# Radii.net
KiCad netlist of a schematic drawn in EAGLE
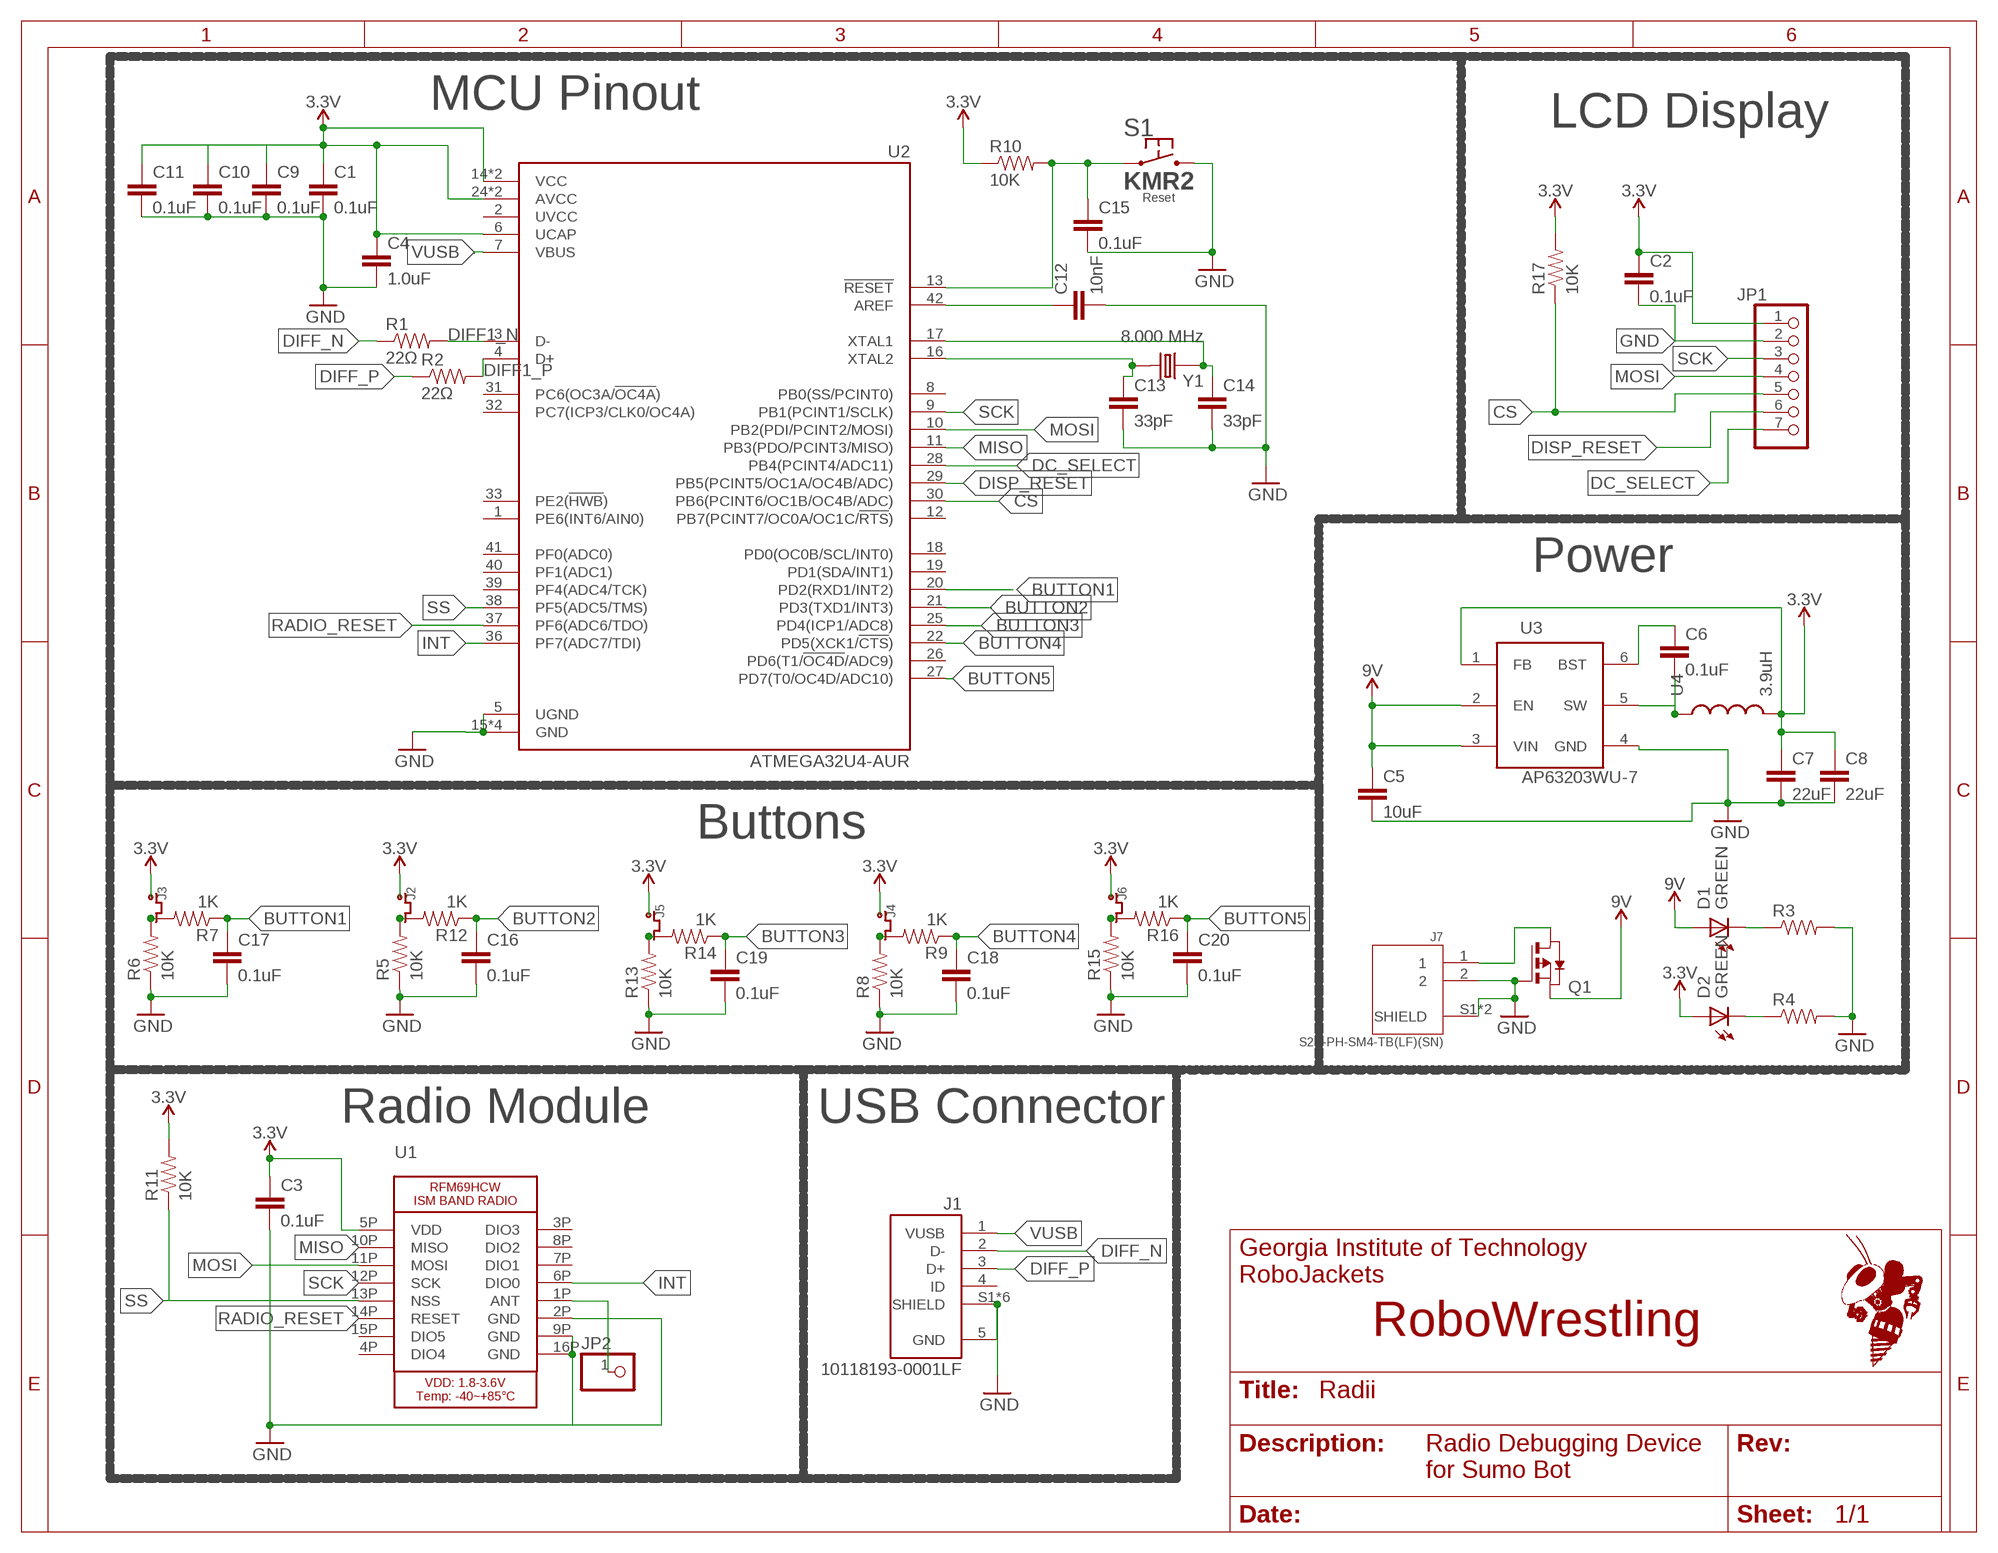
[diagram p0: schematic, sheet 1]

(export (version "E")
  (design (tool "Eeschema 10.0.6"))
  (components
    (comp (ref "C1")
      (value "0.1uF")
      (footprint "eagle-import:0603")
      (libsource (lib "eagle-import") (part "0.1UF-0603-25V-(+80/-20%)"))
    )
    (comp (ref "C2")
      (value "0.1uF")
      (footprint "eagle-import:0603")
      (libsource (lib "eagle-import") (part "0.1UF-0603-25V-(+80/-20%)"))
    )
    (comp (ref "C3")
      (value "0.1uF")
      (footprint "eagle-import:0603")
      (libsource (lib "eagle-import") (part "0.1UF-0603-25V-(+80/-20%)"))
    )
    (comp (ref "C4")
      (value "1.0uF")
      (footprint "eagle-import:0603")
      (libsource (lib "eagle-import") (part "1.0UF-0603-16V-10%"))
    )
    (comp (ref "C5")
      (value "10uF")
      (footprint "eagle-import:0603")
      (libsource (lib "eagle-import") (part "10UF-0603-6.3V-20%"))
    )
    (comp (ref "C6")
      (value "0.1uF")
      (footprint "eagle-import:0603")
      (libsource (lib "eagle-import") (part "0.1UF-0603-25V-(+80/-20%)"))
    )
    (comp (ref "C7")
      (value "22uF")
      (footprint "eagle-import:1210")
      (libsource (lib "eagle-import") (part "22UF-1210-16V-20%"))
    )
    (comp (ref "C8")
      (value "22uF")
      (footprint "eagle-import:1210")
      (libsource (lib "eagle-import") (part "22UF-1210-16V-20%"))
    )
    (comp (ref "C9")
      (value "0.1uF")
      (footprint "eagle-import:0603")
      (libsource (lib "eagle-import") (part "0.1UF-0603-25V-(+80/-20%)"))
    )
    (comp (ref "C10")
      (value "0.1uF")
      (footprint "eagle-import:0603")
      (libsource (lib "eagle-import") (part "0.1UF-0603-25V-(+80/-20%)"))
    )
    (comp (ref "C11")
      (value "0.1uF")
      (footprint "eagle-import:0603")
      (libsource (lib "eagle-import") (part "0.1UF-0603-25V-(+80/-20%)"))
    )
    (comp (ref "C12")
      (value "10nF")
      (footprint "eagle-import:0603")
      (libsource (lib "eagle-import") (part "10NF-0603-50V-10%"))
    )
    (comp (ref "C13")
      (value "33pF")
      (footprint "eagle-import:0603")
      (libsource (lib "eagle-import") (part "33PF-0603-50V-5%"))
    )
    (comp (ref "C14")
      (value "33pF")
      (footprint "eagle-import:0603")
      (libsource (lib "eagle-import") (part "33PF-0603-50V-5%"))
    )
    (comp (ref "C15")
      (value "0.1uF")
      (footprint "eagle-import:0603")
      (libsource (lib "eagle-import") (part "0.1UF-0603-25V-(+80/-20%)"))
    )
    (comp (ref "C16")
      (value "0.1uF")
      (footprint "eagle-import:0603")
      (libsource (lib "eagle-import") (part "0.1UF-0603-25V-(+80/-20%)"))
    )
    (comp (ref "C17")
      (value "0.1uF")
      (footprint "eagle-import:0603")
      (libsource (lib "eagle-import") (part "0.1UF-0603-25V-(+80/-20%)"))
    )
    (comp (ref "C18")
      (value "0.1uF")
      (footprint "eagle-import:0603")
      (libsource (lib "eagle-import") (part "0.1UF-0603-25V-(+80/-20%)"))
    )
    (comp (ref "C19")
      (value "0.1uF")
      (footprint "eagle-import:0603")
      (libsource (lib "eagle-import") (part "0.1UF-0603-25V-(+80/-20%)"))
    )
    (comp (ref "C20")
      (value "0.1uF")
      (footprint "eagle-import:0603")
      (libsource (lib "eagle-import") (part "0.1UF-0603-25V-(+80/-20%)"))
    )
    (comp (ref "D1")
      (value "GREEN")
      (footprint "eagle-import:CHIP-LED0603")
      (libsource (lib "eagle-import") (part "LED-SMD"))
    )
    (comp (ref "D2")
      (value "GREEN")
      (footprint "eagle-import:CHIP-LED0603")
      (libsource (lib "eagle-import") (part "LED-SMD"))
    )
    (comp (ref "J1")
      (value "10118193-0001LF")
      (footprint "eagle-import:FCI_10118193-0001LF")
      (libsource (lib "eagle-import") (part "10118193-0001LF"))
    )
    (comp (ref "J2")
      (value "BUTTON")
      (footprint "eagle-import:1X02")
      (libsource (lib "eagle-import") (part "BUTTON"))
    )
    (comp (ref "J3")
      (value "BUTTON")
      (footprint "eagle-import:1X02")
      (libsource (lib "eagle-import") (part "BUTTON"))
    )
    (comp (ref "J4")
      (value "BUTTON")
      (footprint "eagle-import:1X02")
      (libsource (lib "eagle-import") (part "BUTTON"))
    )
    (comp (ref "J5")
      (value "BUTTON")
      (footprint "eagle-import:1X02")
      (libsource (lib "eagle-import") (part "BUTTON"))
    )
    (comp (ref "J6")
      (value "BUTTON")
      (footprint "eagle-import:1X02")
      (libsource (lib "eagle-import") (part "BUTTON"))
    )
    (comp (ref "J7")
      (value "S2B-PH-SM4-TB(LF)(SN)")
      (footprint "eagle-import:JST_S2B-PH-SM4-TB(LF)(SN)")
      (fields (field (name "DIGI-KEY_PART_NUMBER") "455-1749-1-ND"))
      (libsource (lib "eagle-import") (part "S2B-PH-SM4-TB(LF)(SN)"))
    )
    (comp (ref "JP1")
      (value "PINHD-1X7")
      (footprint "eagle-import:1X07")
      (libsource (lib "eagle-import") (part "PINHD-1X7"))
    )
    (comp (ref "JP2")
      (value "PINHD-1X1")
      (footprint "eagle-import:1X01")
      (libsource (lib "eagle-import") (part "PINHD-1X1"))
    )
    (comp (ref "Q1")
      (value "PMOS")
      (footprint "eagle-import:SOT-23-3")
      (libsource (lib "eagle-import") (part "PMOS"))
    )
    (comp (ref "R1")
      (value "22Ω")
      (footprint "eagle-import:0603-RES")
      (libsource (lib "eagle-import") (part "22OHM1/10W1%(0603)"))
    )
    (comp (ref "R2")
      (value "22Ω")
      (footprint "eagle-import:0603-RES")
      (libsource (lib "eagle-import") (part "22OHM1/10W1%(0603)"))
    )
    (comp (ref "R3")
      (value "RESISTOR0603")
      (footprint "eagle-import:0603")
      (libsource (lib "eagle-import") (part "RESISTOR0603"))
    )
    (comp (ref "R4")
      (value "RESISTOR0603")
      (footprint "eagle-import:0603")
      (libsource (lib "eagle-import") (part "RESISTOR0603"))
    )
    (comp (ref "R5")
      (value "10K")
      (footprint "eagle-import:0603-RES")
      (libsource (lib "eagle-import") (part "10KOHM-1/10W-1%(0603)0603"))
    )
    (comp (ref "R6")
      (value "10K")
      (footprint "eagle-import:0603-RES")
      (libsource (lib "eagle-import") (part "10KOHM-1/10W-1%(0603)0603"))
    )
    (comp (ref "R7")
      (value "1K")
      (footprint "eagle-import:0603-RES")
      (libsource (lib "eagle-import") (part "10KOHM-1/10W-1%(0603)0603"))
    )
    (comp (ref "R8")
      (value "10K")
      (footprint "eagle-import:0603-RES")
      (libsource (lib "eagle-import") (part "10KOHM-1/10W-1%(0603)0603"))
    )
    (comp (ref "R9")
      (value "1K")
      (footprint "eagle-import:0603-RES")
      (libsource (lib "eagle-import") (part "10KOHM-1/10W-1%(0603)0603"))
    )
    (comp (ref "R10")
      (value "10K")
      (footprint "eagle-import:0603-RES")
      (libsource (lib "eagle-import") (part "10KOHM-1/10W-1%(0603)0603"))
    )
    (comp (ref "R11")
      (value "10K")
      (footprint "eagle-import:0603-RES")
      (libsource (lib "eagle-import") (part "10KOHM-1/10W-1%(0603)0603"))
    )
    (comp (ref "R12")
      (value "1K")
      (footprint "eagle-import:0603-RES")
      (libsource (lib "eagle-import") (part "10KOHM-1/10W-1%(0603)0603"))
    )
    (comp (ref "R13")
      (value "10K")
      (footprint "eagle-import:0603-RES")
      (libsource (lib "eagle-import") (part "10KOHM-1/10W-1%(0603)0603"))
    )
    (comp (ref "R14")
      (value "1K")
      (footprint "eagle-import:0603-RES")
      (libsource (lib "eagle-import") (part "10KOHM-1/10W-1%(0603)0603"))
    )
    (comp (ref "R15")
      (value "10K")
      (footprint "eagle-import:0603-RES")
      (libsource (lib "eagle-import") (part "10KOHM-1/10W-1%(0603)0603"))
    )
    (comp (ref "R16")
      (value "1K")
      (footprint "eagle-import:0603-RES")
      (libsource (lib "eagle-import") (part "10KOHM-1/10W-1%(0603)0603"))
    )
    (comp (ref "R17")
      (value "10K")
      (footprint "eagle-import:0603-RES")
      (libsource (lib "eagle-import") (part "10KOHM-1/10W-1%(0603)0603"))
    )
    (comp (ref "S1")
      (value "KMR2")
      (footprint "eagle-import:KMR2")
      (fields (field (name "FUNCTION") "Reset"))
      (libsource (lib "eagle-import") (part "KMR2"))
    )
    (comp (ref "U1")
      (value "RFM69HCW_SMT")
      (footprint "eagle-import:RFMHCW_SMT")
      (libsource (lib "eagle-import") (part "RFM69HCW_SMT"))
    )
    (comp (ref "U2")
      (value "ATMEGA32U4-AUR")
      (footprint "eagle-import:44-TQFP(10X10)")
      (libsource (lib "eagle-import") (part "ATMEGA32U4-AUR"))
    )
    (comp (ref "U3")
      (value "AP63203WU-7")
      (footprint "eagle-import:TSOT-23-6")
      (libsource (lib "eagle-import") (part "AP63203WU-7"))
    )
    (comp (ref "U4")
      (value "3.9uH")
      (footprint "eagle-import:1255AY-3R9N=P3")
      (fields (field (name "TOLERANCE") "±30%"))
      (libsource (lib "eagle-import") (part "1255AY-3R9N=P3"))
    )
    (comp (ref "Y1")
      (value "8.000 MHz")
      (footprint "eagle-import:XTAL_ECS-80-20-5PX-TR")
      (libsource (lib "eagle-import") (part "ECS-80-20-5PX-TR"))
    )
  )
  (nets
    (net (code "1") (name "/DIFF1_N") (class "Default")
      (node (ref "R1") (pin "2") (pinfunction "2_2") (pintype "passive"))
      (node (ref "U2") (pin "3") (pinfunction "D-_3") (pintype "passive"))
    )
    (net (code "2") (name "/DIFF1_P") (class "Default")
      (node (ref "R2") (pin "2") (pinfunction "2_2") (pintype "passive"))
      (node (ref "U2") (pin "4") (pinfunction "D+_4") (pintype "passive"))
    )
    (net (code "3") (name "3.3V") (class "Default")
      (node (ref "C1") (pin "1") (pinfunction "1_1") (pintype "passive"))
      (node (ref "C10") (pin "1") (pinfunction "1_1") (pintype "passive"))
      (node (ref "C11") (pin "1") (pinfunction "1_1") (pintype "passive"))
      (node (ref "C2") (pin "1") (pinfunction "1_1") (pintype "passive"))
      (node (ref "C3") (pin "1") (pinfunction "1_1") (pintype "passive"))
      (node (ref "C4") (pin "1") (pinfunction "1_1") (pintype "passive"))
      (node (ref "C7") (pin "1") (pinfunction "1_1") (pintype "passive"))
      (node (ref "C8") (pin "1") (pinfunction "1_1") (pintype "passive"))
      (node (ref "C9") (pin "1") (pinfunction "1_1") (pintype "passive"))
      (node (ref "D2") (pin "A") (pinfunction "A_A") (pintype "passive"))
      (node (ref "J2") (pin "1") (pinfunction "P$1_1") (pintype "passive"))
      (node (ref "J3") (pin "1") (pinfunction "P$1_1") (pintype "passive"))
      (node (ref "J4") (pin "1") (pinfunction "P$1_1") (pintype "passive"))
      (node (ref "J5") (pin "1") (pinfunction "P$1_1") (pintype "passive"))
      (node (ref "J6") (pin "1") (pinfunction "P$1_1") (pintype "passive"))
      (node (ref "JP1") (pin "1") (pinfunction "1_1") (pintype "passive"))
      (node (ref "R10") (pin "1") (pinfunction "1_1") (pintype "passive"))
      (node (ref "R11") (pin "2") (pinfunction "2_2") (pintype "passive"))
      (node (ref "R17") (pin "2") (pinfunction "2_2") (pintype "passive"))
      (node (ref "U1") (pin "5P") (pinfunction "VDD_5P") (pintype "passive"))
      (node (ref "U2") (pin "14") (pinfunction "VCC_14") (pintype "passive"))
      (node (ref "U2") (pin "24") (pinfunction "AVCC_24") (pintype "passive"))
      (node (ref "U2") (pin "34") (pinfunction "VCC_34") (pintype "passive"))
      (node (ref "U2") (pin "44") (pinfunction "AVCC_44") (pintype "passive"))
      (node (ref "U2") (pin "6") (pinfunction "UCAP_6") (pintype "passive"))
      (node (ref "U3") (pin "1") (pinfunction "FB_1") (pintype "passive"))
      (node (ref "U4") (pin "2") (pinfunction "2_2") (pintype "passive"))
    )
    (net (code "4") (name "9V") (class "Default")
      (node (ref "C5") (pin "1") (pinfunction "1_1") (pintype "passive"))
      (node (ref "D1") (pin "A") (pinfunction "A_A") (pintype "passive"))
      (node (ref "Q1") (pin "2") (pinfunction "S_2") (pintype "passive"))
      (node (ref "U3") (pin "2") (pinfunction "EN_2") (pintype "passive"))
      (node (ref "U3") (pin "3") (pinfunction "VIN_3") (pintype "passive"))
    )
    (net (code "5") (name "BUTTON1") (class "Default")
      (node (ref "C17") (pin "1") (pinfunction "1_1") (pintype "passive"))
      (node (ref "R7") (pin "1") (pinfunction "1_1") (pintype "passive"))
      (node (ref "U2") (pin "20") (pinfunction "PD2(RXD1/INT2)_20") (pintype "passive"))
    )
    (net (code "6") (name "BUTTON2") (class "Default")
      (node (ref "C16") (pin "1") (pinfunction "1_1") (pintype "passive"))
      (node (ref "R12") (pin "1") (pinfunction "1_1") (pintype "passive"))
      (node (ref "U2") (pin "21") (pinfunction "PD3(TXD1/INT3)_21") (pintype "passive"))
    )
    (net (code "7") (name "BUTTON3") (class "Default")
      (node (ref "C19") (pin "1") (pinfunction "1_1") (pintype "passive"))
      (node (ref "R14") (pin "1") (pinfunction "1_1") (pintype "passive"))
      (node (ref "U2") (pin "25") (pinfunction "PD4(ICP1/ADC8)_25") (pintype "passive"))
    )
    (net (code "8") (name "BUTTON4") (class "Default")
      (node (ref "C18") (pin "1") (pinfunction "1_1") (pintype "passive"))
      (node (ref "R9") (pin "1") (pinfunction "1_1") (pintype "passive"))
      (node (ref "U2") (pin "22") (pinfunction "PD5(XCK1/~{CTS})_22") (pintype "passive"))
    )
    (net (code "9") (name "BUTTON5") (class "Default")
      (node (ref "C20") (pin "1") (pinfunction "1_1") (pintype "passive"))
      (node (ref "R16") (pin "1") (pinfunction "1_1") (pintype "passive"))
      (node (ref "U2") (pin "27") (pinfunction "PD7(T0/OC4D/ADC10)_27") (pintype "passive"))
    )
    (net (code "10") (name "CS") (class "Default")
      (node (ref "JP1") (pin "5") (pinfunction "5_5") (pintype "passive"))
      (node (ref "R17") (pin "1") (pinfunction "1_1") (pintype "passive"))
      (node (ref "U2") (pin "30") (pinfunction "PB6(PCINT6/OC1B/OC4B/ADC)_30") (pintype "passive"))
    )
    (net (code "11") (name "DC_SELECT") (class "Default")
      (node (ref "JP1") (pin "7") (pinfunction "7_7") (pintype "passive"))
      (node (ref "U2") (pin "28") (pinfunction "PB4(PCINT4/ADC11)_28") (pintype "passive"))
    )
    (net (code "12") (name "DIFF_N") (class "Default")
      (node (ref "J1") (pin "2") (pinfunction "D-_2") (pintype "passive"))
      (node (ref "R1") (pin "1") (pinfunction "1_1") (pintype "passive"))
    )
    (net (code "13") (name "DIFF_P") (class "Default")
      (node (ref "J1") (pin "3") (pinfunction "D+_3") (pintype "passive"))
      (node (ref "R2") (pin "1") (pinfunction "1_1") (pintype "passive"))
    )
    (net (code "14") (name "DISP_RESET") (class "Default")
      (node (ref "JP1") (pin "6") (pinfunction "6_6") (pintype "passive"))
      (node (ref "U2") (pin "29") (pinfunction "PB5(PCINT5/OC1A/OC4B/ADC)_29") (pintype "passive"))
    )
    (net (code "15") (name "GND") (class "Default")
      (node (ref "C1") (pin "2") (pinfunction "2_2") (pintype "passive"))
      (node (ref "C10") (pin "2") (pinfunction "2_2") (pintype "passive"))
      (node (ref "C11") (pin "2") (pinfunction "2_2") (pintype "passive"))
      (node (ref "C12") (pin "2") (pinfunction "2_2") (pintype "passive"))
      (node (ref "C13") (pin "2") (pinfunction "2_2") (pintype "passive"))
      (node (ref "C14") (pin "2") (pinfunction "2_2") (pintype "passive"))
      (node (ref "C15") (pin "2") (pinfunction "2_2") (pintype "passive"))
      (node (ref "C16") (pin "2") (pinfunction "2_2") (pintype "passive"))
      (node (ref "C17") (pin "2") (pinfunction "2_2") (pintype "passive"))
      (node (ref "C18") (pin "2") (pinfunction "2_2") (pintype "passive"))
      (node (ref "C19") (pin "2") (pinfunction "2_2") (pintype "passive"))
      (node (ref "C2") (pin "2") (pinfunction "2_2") (pintype "passive"))
      (node (ref "C20") (pin "2") (pinfunction "2_2") (pintype "passive"))
      (node (ref "C3") (pin "2") (pinfunction "2_2") (pintype "passive"))
      (node (ref "C4") (pin "2") (pinfunction "2_2") (pintype "passive"))
      (node (ref "C5") (pin "2") (pinfunction "2_2") (pintype "passive"))
      (node (ref "C7") (pin "2") (pinfunction "2_2") (pintype "passive"))
      (node (ref "C8") (pin "2") (pinfunction "2_2") (pintype "passive"))
      (node (ref "C9") (pin "2") (pinfunction "2_2") (pintype "passive"))
      (node (ref "J1") (pin "5") (pinfunction "GND_5") (pintype "passive"))
      (node (ref "J1") (pin "S1") (pinfunction "SHIELD_S1") (pintype "passive"))
      (node (ref "J1") (pin "S2") (pinfunction "SHIELD_S2") (pintype "passive"))
      (node (ref "J1") (pin "S3") (pinfunction "SHIELD_S3") (pintype "passive"))
      (node (ref "J1") (pin "S4") (pinfunction "SHIELD_S4") (pintype "passive"))
      (node (ref "J1") (pin "S5") (pinfunction "SHIELD_S5") (pintype "passive"))
      (node (ref "J1") (pin "S6") (pinfunction "SHIELD_S6") (pintype "passive"))
      (node (ref "J7") (pin "2") (pinfunction "2_2") (pintype "passive"))
      (node (ref "J7") (pin "S1") (pinfunction "SHIELD_S1") (pintype "passive"))
      (node (ref "J7") (pin "S2") (pinfunction "SHIELD_S2") (pintype "passive"))
      (node (ref "JP1") (pin "2") (pinfunction "2_2") (pintype "passive"))
      (node (ref "Q1") (pin "1") (pinfunction "G_1") (pintype "passive"))
      (node (ref "R13") (pin "1") (pinfunction "1_1") (pintype "passive"))
      (node (ref "R15") (pin "1") (pinfunction "1_1") (pintype "passive"))
      (node (ref "R3") (pin "2") (pinfunction "2_2") (pintype "passive"))
      (node (ref "R4") (pin "2") (pinfunction "2_2") (pintype "passive"))
      (node (ref "R5") (pin "1") (pinfunction "1_1") (pintype "passive"))
      (node (ref "R6") (pin "1") (pinfunction "1_1") (pintype "passive"))
      (node (ref "R8") (pin "1") (pinfunction "1_1") (pintype "passive"))
      (node (ref "S1") (pin "2.1") (pinfunction "2_2.1") (pintype "passive"))
      (node (ref "S1") (pin "2.2") (pinfunction "2_2.2") (pintype "passive"))
      (node (ref "U1") (pin "16P") (pinfunction "GND_16P") (pintype "passive"))
      (node (ref "U1") (pin "2P") (pinfunction "GND_2P") (pintype "passive"))
      (node (ref "U1") (pin "9P") (pinfunction "GND_9P") (pintype "passive"))
      (node (ref "U2") (pin "15") (pinfunction "GND_15") (pintype "passive"))
      (node (ref "U2") (pin "23") (pinfunction "GND_23") (pintype "passive"))
      (node (ref "U2") (pin "35") (pinfunction "GND_35") (pintype "passive"))
      (node (ref "U2") (pin "43") (pinfunction "GND_43") (pintype "passive"))
      (node (ref "U2") (pin "5") (pinfunction "UGND_5") (pintype "passive"))
      (node (ref "U3") (pin "4") (pinfunction "GND_4") (pintype "passive"))
    )
    (net (code "16") (name "INT") (class "Default")
      (node (ref "U1") (pin "6P") (pinfunction "DIO0_6P") (pintype "passive"))
      (node (ref "U2") (pin "36") (pinfunction "PF7(ADC7/TDI)_36") (pintype "passive"))
    )
    (net (code "17") (name "MISO") (class "Default")
      (node (ref "U1") (pin "10P") (pinfunction "MISO_10P") (pintype "passive"))
      (node (ref "U2") (pin "11") (pinfunction "PB3(PDO/PCINT3/MISO)_11") (pintype "passive"))
    )
    (net (code "18") (name "MOSI") (class "Default")
      (node (ref "JP1") (pin "4") (pinfunction "4_4") (pintype "passive"))
      (node (ref "U1") (pin "11P") (pinfunction "MOSI_11P") (pintype "passive"))
      (node (ref "U2") (pin "10") (pinfunction "PB2(PDI/PCINT2/MOSI)_10") (pintype "passive"))
    )
    (net (code "19") (name "Net-(D1-K)") (class "Default")
      (node (ref "D1") (pin "C") (pinfunction "K_C") (pintype "passive"))
      (node (ref "R3") (pin "1") (pinfunction "1_1") (pintype "passive"))
    )
    (net (code "20") (name "Net-(D2-K)") (class "Default")
      (node (ref "D2") (pin "C") (pinfunction "K_C") (pintype "passive"))
      (node (ref "R4") (pin "1") (pinfunction "1_1") (pintype "passive"))
    )
    (net (code "21") (name "Net-(J2-P$2)") (class "Default")
      (node (ref "J2") (pin "2") (pinfunction "P$2_2") (pintype "passive"))
      (node (ref "R12") (pin "2") (pinfunction "2_2") (pintype "passive"))
      (node (ref "R5") (pin "2") (pinfunction "2_2") (pintype "passive"))
    )
    (net (code "22") (name "Net-(J3-P$2)") (class "Default")
      (node (ref "J3") (pin "2") (pinfunction "P$2_2") (pintype "passive"))
      (node (ref "R6") (pin "2") (pinfunction "2_2") (pintype "passive"))
      (node (ref "R7") (pin "2") (pinfunction "2_2") (pintype "passive"))
    )
    (net (code "23") (name "Net-(J4-P$2)") (class "Default")
      (node (ref "J4") (pin "2") (pinfunction "P$2_2") (pintype "passive"))
      (node (ref "R8") (pin "2") (pinfunction "2_2") (pintype "passive"))
      (node (ref "R9") (pin "2") (pinfunction "2_2") (pintype "passive"))
    )
    (net (code "24") (name "Net-(J5-P$2)") (class "Default")
      (node (ref "J5") (pin "2") (pinfunction "P$2_2") (pintype "passive"))
      (node (ref "R13") (pin "2") (pinfunction "2_2") (pintype "passive"))
      (node (ref "R14") (pin "2") (pinfunction "2_2") (pintype "passive"))
    )
    (net (code "25") (name "Net-(J6-P$2)") (class "Default")
      (node (ref "J6") (pin "2") (pinfunction "P$2_2") (pintype "passive"))
      (node (ref "R15") (pin "2") (pinfunction "2_2") (pintype "passive"))
      (node (ref "R16") (pin "2") (pinfunction "2_2") (pintype "passive"))
    )
    (net (code "26") (name "Net-(Q1-D)") (class "Default")
      (node (ref "J7") (pin "1") (pinfunction "1_1") (pintype "passive"))
      (node (ref "Q1") (pin "3") (pinfunction "D_3") (pintype "passive"))
    )
    (net (code "27") (name "Net-(U1-ANT)") (class "Default")
      (node (ref "JP2") (pin "1") (pinfunction "1_1") (pintype "passive"))
      (node (ref "U1") (pin "1P") (pinfunction "ANT_1P") (pintype "passive"))
    )
    (net (code "28") (name "Net-(U2-AREF)") (class "Default")
      (node (ref "C12") (pin "1") (pinfunction "1_1") (pintype "passive"))
      (node (ref "U2") (pin "42") (pinfunction "AREF_42") (pintype "passive"))
    )
    (net (code "29") (name "Net-(U2-XTAL1)") (class "Default")
      (node (ref "C14") (pin "1") (pinfunction "1_1") (pintype "passive"))
      (node (ref "U2") (pin "17") (pinfunction "XTAL1_17") (pintype "passive"))
      (node (ref "Y1") (pin "1") (pinfunction "1_1") (pintype "passive"))
    )
    (net (code "30") (name "Net-(U2-XTAL2)") (class "Default")
      (node (ref "C13") (pin "1") (pinfunction "1_1") (pintype "passive"))
      (node (ref "U2") (pin "16") (pinfunction "XTAL2_16") (pintype "passive"))
      (node (ref "Y1") (pin "2") (pinfunction "2_2") (pintype "passive"))
    )
    (net (code "31") (name "Net-(U2-~{RESET})") (class "Default")
      (node (ref "C15") (pin "1") (pinfunction "1_1") (pintype "passive"))
      (node (ref "R10") (pin "2") (pinfunction "2_2") (pintype "passive"))
      (node (ref "S1") (pin "1.1") (pinfunction "1_1.1") (pintype "passive"))
      (node (ref "S1") (pin "1.2") (pinfunction "1_1.2") (pintype "passive"))
      (node (ref "U2") (pin "13") (pinfunction "~{RESET}_13") (pintype "passive"))
    )
    (net (code "32") (name "Net-(U3-BST)") (class "Default")
      (node (ref "C6") (pin "1") (pinfunction "1_1") (pintype "passive"))
      (node (ref "U3") (pin "6") (pinfunction "BST_6") (pintype "passive"))
    )
    (net (code "33") (name "Net-(U3-SW)") (class "Default")
      (node (ref "C6") (pin "2") (pinfunction "2_2") (pintype "passive"))
      (node (ref "U3") (pin "5") (pinfunction "SW_5") (pintype "passive"))
      (node (ref "U4") (pin "1") (pinfunction "1_1") (pintype "passive"))
    )
    (net (code "34") (name "RADIO_RESET") (class "Default")
      (node (ref "U1") (pin "14P") (pinfunction "RESET_14P") (pintype "passive"))
      (node (ref "U2") (pin "37") (pinfunction "PF6(ADC6/TDO)_37") (pintype "passive"))
    )
    (net (code "35") (name "SCK") (class "Default")
      (node (ref "JP1") (pin "3") (pinfunction "3_3") (pintype "passive"))
      (node (ref "U1") (pin "12P") (pinfunction "SCK_12P") (pintype "passive"))
      (node (ref "U2") (pin "9") (pinfunction "PB1(PCINT1/SCLK)_9") (pintype "passive"))
    )
    (net (code "36") (name "SS") (class "Default")
      (node (ref "R11") (pin "1") (pinfunction "1_1") (pintype "passive"))
      (node (ref "U1") (pin "13P") (pinfunction "NSS_13P") (pintype "passive"))
      (node (ref "U2") (pin "38") (pinfunction "PF5(ADC5/TMS)_38") (pintype "passive"))
    )
    (net (code "37") (name "VUSB") (class "Default")
      (node (ref "J1") (pin "1") (pinfunction "VUSB_1") (pintype "passive"))
      (node (ref "U2") (pin "7") (pinfunction "VBUS_7") (pintype "passive"))
    )
    (net (code "38") (name "unconnected-(J1-ID-Pad4)") (class "Default")
      (node (ref "J1") (pin "4") (pinfunction "ID_4") (pintype "passive"))
    )
    (net (code "39") (name "unconnected-(U1-DIO1-Pad7P)") (class "Default")
      (node (ref "U1") (pin "7P") (pinfunction "DIO1_7P") (pintype "passive"))
    )
    (net (code "40") (name "unconnected-(U1-DIO2-Pad8P)") (class "Default")
      (node (ref "U1") (pin "8P") (pinfunction "DIO2_8P") (pintype "passive"))
    )
    (net (code "41") (name "unconnected-(U1-DIO3-Pad3P)") (class "Default")
      (node (ref "U1") (pin "3P") (pinfunction "DIO3_3P") (pintype "passive"))
    )
    (net (code "42") (name "unconnected-(U1-DIO4-Pad4P)") (class "Default")
      (node (ref "U1") (pin "4P") (pinfunction "DIO4_4P") (pintype "passive"))
    )
    (net (code "43") (name "unconnected-(U1-DIO5-Pad15P)") (class "Default")
      (node (ref "U1") (pin "15P") (pinfunction "DIO5_15P") (pintype "passive"))
    )
    (net (code "44") (name "unconnected-(U2-PB0(SS{slash}PCINT0)-Pad8)") (class "Default")
      (node (ref "U2") (pin "8") (pinfunction "PB0(SS/PCINT0)_8") (pintype "passive"))
    )
    (net (code "45") (name "unconnected-(U2-PB7(PCINT7{slash}OC0A{slash}OC1C{slash}~{RTS})-Pad12)") (class "Default")
      (node (ref "U2") (pin "12") (pinfunction "PB7(PCINT7/OC0A/OC1C/~{RTS})_12") (pintype "passive"))
    )
    (net (code "46") (name "unconnected-(U2-PC6(OC3A{slash}~{OC4A})-Pad31)") (class "Default")
      (node (ref "U2") (pin "31") (pinfunction "PC6(OC3A/~{OC4A})_31") (pintype "passive"))
    )
    (net (code "47") (name "unconnected-(U2-PC7(ICP3{slash}CLK0{slash}OC4A)-Pad32)") (class "Default")
      (node (ref "U2") (pin "32") (pinfunction "PC7(ICP3/CLK0/OC4A)_32") (pintype "passive"))
    )
    (net (code "48") (name "unconnected-(U2-PD0(OC0B{slash}SCL{slash}INT0)-Pad18)") (class "Default")
      (node (ref "U2") (pin "18") (pinfunction "PD0(OC0B/SCL/INT0)_18") (pintype "passive"))
    )
    (net (code "49") (name "unconnected-(U2-PD1(SDA{slash}INT1)-Pad19)") (class "Default")
      (node (ref "U2") (pin "19") (pinfunction "PD1(SDA/INT1)_19") (pintype "passive"))
    )
    (net (code "50") (name "unconnected-(U2-PD6(T1{slash}~{OC4D}{slash}ADC9)-Pad26)") (class "Default")
      (node (ref "U2") (pin "26") (pinfunction "PD6(T1/~{OC4D}/ADC9)_26") (pintype "passive"))
    )
    (net (code "51") (name "unconnected-(U2-PE2(~{HWB})-Pad33)") (class "Default")
      (node (ref "U2") (pin "33") (pinfunction "PE2(~{HWB})_33") (pintype "passive"))
    )
    (net (code "52") (name "unconnected-(U2-PE6(INT6{slash}AIN0)-Pad1)") (class "Default")
      (node (ref "U2") (pin "1") (pinfunction "PE6(INT6/AIN0)_1") (pintype "passive"))
    )
    (net (code "53") (name "unconnected-(U2-PF0(ADC0)-Pad41)") (class "Default")
      (node (ref "U2") (pin "41") (pinfunction "PF0(ADC0)_41") (pintype "passive"))
    )
    (net (code "54") (name "unconnected-(U2-PF1(ADC1)-Pad40)") (class "Default")
      (node (ref "U2") (pin "40") (pinfunction "PF1(ADC1)_40") (pintype "passive"))
    )
    (net (code "55") (name "unconnected-(U2-PF4(ADC4{slash}TCK)-Pad39)") (class "Default")
      (node (ref "U2") (pin "39") (pinfunction "PF4(ADC4/TCK)_39") (pintype "passive"))
    )
    (net (code "56") (name "unconnected-(U2-UVCC-Pad2)") (class "Default")
      (node (ref "U2") (pin "2") (pinfunction "UVCC_2") (pintype "passive"))
    )
  )
)
